# voice_board_kombi.net
KiCad netlist of a schematic drawn in EAGLE
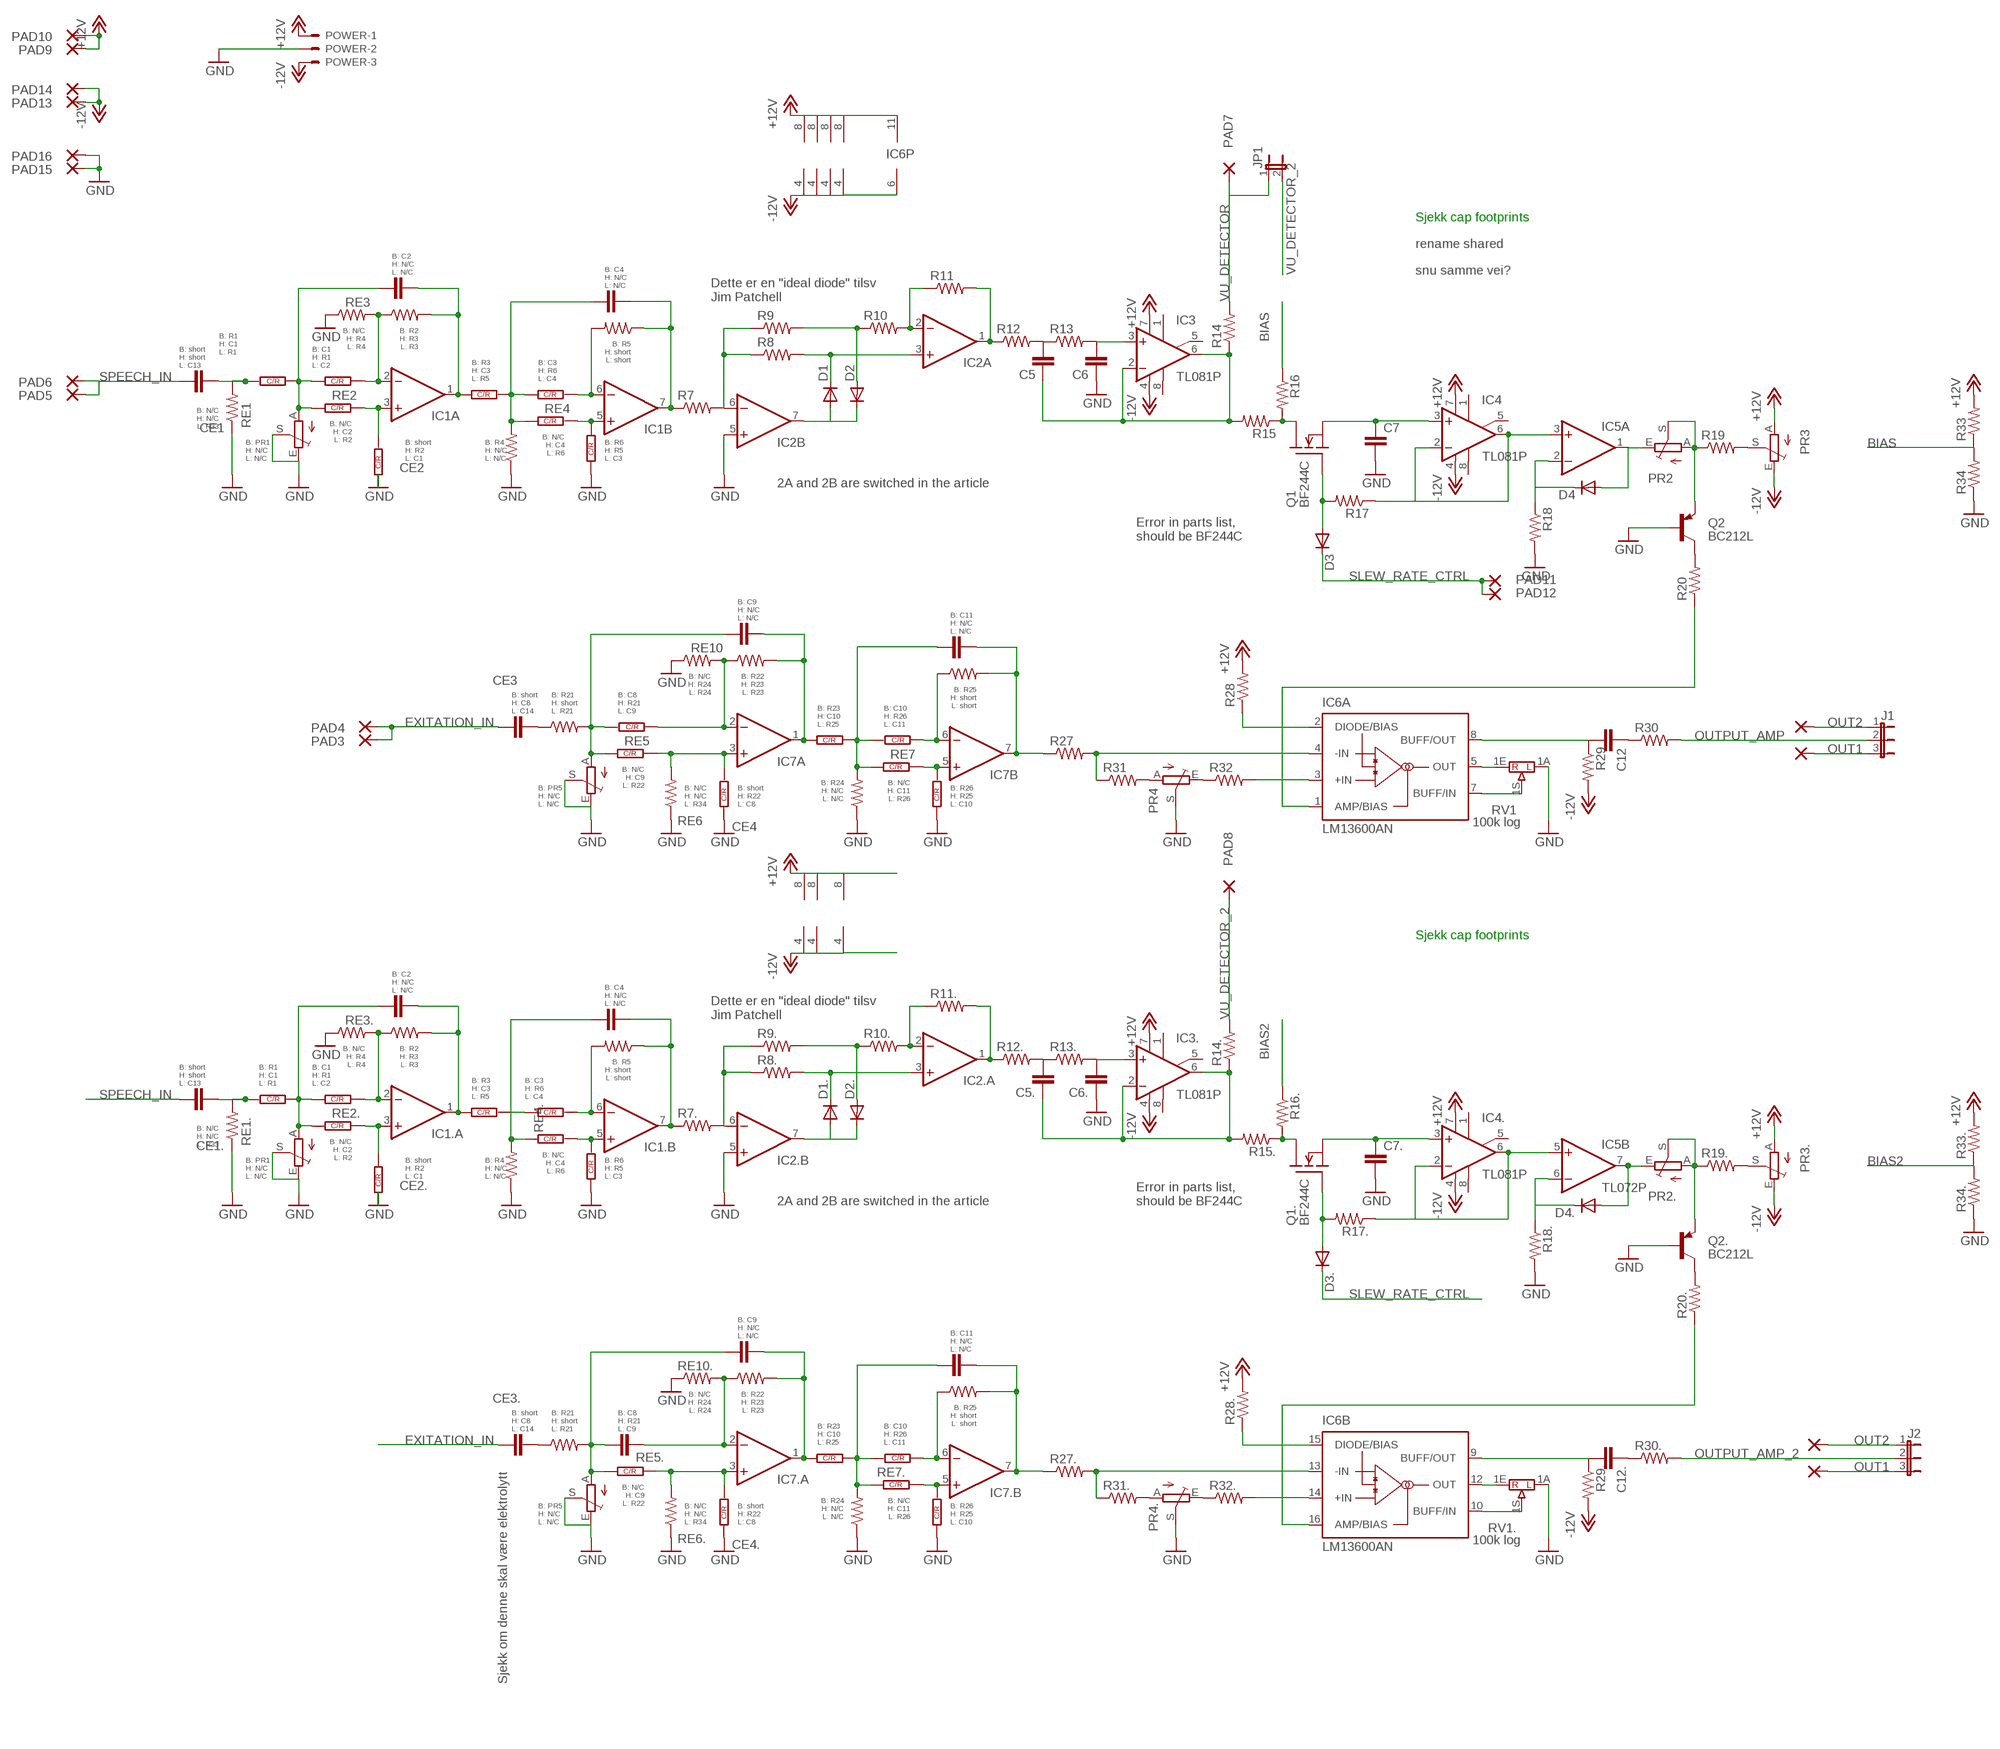
[diagram p0: schematic, sheet 1]

(export (version "E")
  (design (tool "Eeschema 10.0.6"))
  (components
    (comp (ref "C1")
      (value "C-OR-R050_075-025X100")
      (footprint "eagle-import:P050_075-025X100J")
      (libsource (lib "eagle-import") (part "C-OR-R050_075-025X100"))
    )
    (comp (ref "C1.")
      (value "C-OR-R050_075-025X100")
      (footprint "eagle-import:P050_075-025X100J")
      (libsource (lib "eagle-import") (part "C-OR-R050_075-025X100"))
    )
    (comp (ref "C2")
      (value "C-EU050_075-025X100")
      (footprint "eagle-import:C050_075-025X100J")
      (libsource (lib "eagle-import") (part "C-EU050_075-025X100"))
    )
    (comp (ref "C2.")
      (value "C-EU050_075-025X100")
      (footprint "eagle-import:C050_075-025X100J")
      (libsource (lib "eagle-import") (part "C-EU050_075-025X100"))
    )
    (comp (ref "C3")
      (value "C-OR-R050_075-025X100")
      (footprint "eagle-import:P050_075-025X100J")
      (libsource (lib "eagle-import") (part "C-OR-R050_075-025X100"))
    )
    (comp (ref "C3.")
      (value "C-OR-R050_075-025X100")
      (footprint "eagle-import:P050_075-025X100J")
      (libsource (lib "eagle-import") (part "C-OR-R050_075-025X100"))
    )
    (comp (ref "C4")
      (value "C-EU050_075-025X100")
      (footprint "eagle-import:C050_075-025X100J")
      (libsource (lib "eagle-import") (part "C-EU050_075-025X100"))
    )
    (comp (ref "C4.")
      (value "C-EU050_075-025X100")
      (footprint "eagle-import:C050_075-025X100J")
      (libsource (lib "eagle-import") (part "C-EU050_075-025X100"))
    )
    (comp (ref "C5")
      (value "C-EU050_075-025X100")
      (footprint "eagle-import:C050_075-025X100J")
      (libsource (lib "eagle-import") (part "C-EU050_075-025X100"))
    )
    (comp (ref "C5.")
      (value "C-EU050_075-025X100")
      (footprint "eagle-import:C050_075-025X100J")
      (libsource (lib "eagle-import") (part "C-EU050_075-025X100"))
    )
    (comp (ref "C6")
      (value "C-EU050_075-025X100")
      (footprint "eagle-import:C050_075-025X100J")
      (libsource (lib "eagle-import") (part "C-EU050_075-025X100"))
    )
    (comp (ref "C6.")
      (value "C-EU050_075-025X100")
      (footprint "eagle-import:C050_075-025X100J")
      (libsource (lib "eagle-import") (part "C-EU050_075-025X100"))
    )
    (comp (ref "C7")
      (value "C-EU050_075-025X100")
      (footprint "eagle-import:C050_075-025X100J")
      (libsource (lib "eagle-import") (part "C-EU050_075-025X100"))
    )
    (comp (ref "C7.")
      (value "C-EU050_075-025X100")
      (footprint "eagle-import:C050_075-025X100J")
      (libsource (lib "eagle-import") (part "C-EU050_075-025X100"))
    )
    (comp (ref "C8")
      (value "C-OR-R050_075-025X100")
      (footprint "eagle-import:P050_075-025X100J")
      (libsource (lib "eagle-import") (part "C-OR-R050_075-025X100"))
    )
    (comp (ref "C8.")
      (value "C-EU050_075-025X100")
      (footprint "eagle-import:C050_075-025X100J")
      (libsource (lib "eagle-import") (part "C-EU050_075-025X100"))
    )
    (comp (ref "C9")
      (value "C-EU050_075-025X100")
      (footprint "eagle-import:C050_075-025X100J")
      (libsource (lib "eagle-import") (part "C-EU050_075-025X100"))
    )
    (comp (ref "C9.")
      (value "C-EU050_075-025X100")
      (footprint "eagle-import:C050_075-025X100J")
      (libsource (lib "eagle-import") (part "C-EU050_075-025X100"))
    )
    (comp (ref "C10")
      (value "C-OR-R050_075-025X100")
      (footprint "eagle-import:P050_075-025X100J")
      (libsource (lib "eagle-import") (part "C-OR-R050_075-025X100"))
    )
    (comp (ref "C10.")
      (value "C-OR-R050_075-025X100")
      (footprint "eagle-import:P050_075-025X100J")
      (libsource (lib "eagle-import") (part "C-OR-R050_075-025X100"))
    )
    (comp (ref "C11")
      (value "C-EU050_075-025X100")
      (footprint "eagle-import:C050_075-025X100J")
      (libsource (lib "eagle-import") (part "C-EU050_075-025X100"))
    )
    (comp (ref "C11.")
      (value "C-EU050_075-025X100")
      (footprint "eagle-import:C050_075-025X100J")
      (libsource (lib "eagle-import") (part "C-EU050_075-025X100"))
    )
    (comp (ref "C12")
      (value "C-EU050_075-025X100")
      (footprint "eagle-import:C050_075-025X100J")
      (libsource (lib "eagle-import") (part "C-EU050_075-025X100"))
    )
    (comp (ref "C12.")
      (value "C-EU050_075-025X100")
      (footprint "eagle-import:C050_075-025X100J")
      (libsource (lib "eagle-import") (part "C-EU050_075-025X100"))
    )
    (comp (ref "CE1")
      (value "C-EU050_075-025X100")
      (footprint "eagle-import:C050_075-025X100J")
      (libsource (lib "eagle-import") (part "C-EU050_075-025X100"))
    )
    (comp (ref "CE1.")
      (value "C-EU050_075-025X100")
      (footprint "eagle-import:C050_075-025X100J")
      (libsource (lib "eagle-import") (part "C-EU050_075-025X100"))
    )
    (comp (ref "CE2")
      (value "C-OR-R050_075-025X100")
      (footprint "eagle-import:P050_075-025X100J")
      (libsource (lib "eagle-import") (part "C-OR-R050_075-025X100"))
    )
    (comp (ref "CE2.")
      (value "C-OR-R050_075-025X100")
      (footprint "eagle-import:P050_075-025X100J")
      (libsource (lib "eagle-import") (part "C-OR-R050_075-025X100"))
    )
    (comp (ref "CE3")
      (value "C-EU050_075-025X100")
      (footprint "eagle-import:C050_075-025X100J")
      (libsource (lib "eagle-import") (part "C-EU050_075-025X100"))
    )
    (comp (ref "CE3.")
      (value "C-EU050_075-025X100")
      (footprint "eagle-import:C050_075-025X100J")
      (libsource (lib "eagle-import") (part "C-EU050_075-025X100"))
    )
    (comp (ref "CE4")
      (value "C-OR-R050_075-025X100")
      (footprint "eagle-import:P050_075-025X100J")
      (libsource (lib "eagle-import") (part "C-OR-R050_075-025X100"))
    )
    (comp (ref "CE4.")
      (value "C-OR-R050_075-025X100")
      (footprint "eagle-import:P050_075-025X100J")
      (libsource (lib "eagle-import") (part "C-OR-R050_075-025X100"))
    )
    (comp (ref "D1")
      (value "DIODE-D-5")
      (footprint "eagle-import:D-5")
      (libsource (lib "eagle-import") (part "DIODE-D-5"))
    )
    (comp (ref "D1.")
      (value "DIODE-D-5")
      (footprint "eagle-import:D-5")
      (libsource (lib "eagle-import") (part "DIODE-D-5"))
    )
    (comp (ref "D2")
      (value "DIODE-D-5")
      (footprint "eagle-import:D-5")
      (libsource (lib "eagle-import") (part "DIODE-D-5"))
    )
    (comp (ref "D2.")
      (value "DIODE-D-5")
      (footprint "eagle-import:D-5")
      (libsource (lib "eagle-import") (part "DIODE-D-5"))
    )
    (comp (ref "D3")
      (value "DIODE-D-5")
      (footprint "eagle-import:D-5")
      (libsource (lib "eagle-import") (part "DIODE-D-5"))
    )
    (comp (ref "D3.")
      (value "DIODE-D-5")
      (footprint "eagle-import:D-5")
      (libsource (lib "eagle-import") (part "DIODE-D-5"))
    )
    (comp (ref "D4")
      (value "DIODE-D-5")
      (footprint "eagle-import:D-5")
      (libsource (lib "eagle-import") (part "DIODE-D-5"))
    )
    (comp (ref "D4.")
      (value "DIODE-D-5")
      (footprint "eagle-import:D-5")
      (libsource (lib "eagle-import") (part "DIODE-D-5"))
    )
    (comp (ref "IC1")
      (value "TL072P")
      (footprint "eagle-import:DIL08")
      (libsource (lib "eagle-import") (part "TL072P"))
    )
    (comp (ref "IC1.")
      (value "TL072P")
      (footprint "eagle-import:DIL08")
      (libsource (lib "eagle-import") (part "TL072P"))
    )
    (comp (ref "IC2")
      (value "TL072P")
      (footprint "eagle-import:DIL08")
      (libsource (lib "eagle-import") (part "TL072P"))
    )
    (comp (ref "IC2.")
      (value "TL072P")
      (footprint "eagle-import:DIL08")
      (libsource (lib "eagle-import") (part "TL072P"))
    )
    (comp (ref "IC3")
      (value "TL081P")
      (footprint "eagle-import:DIL08")
      (libsource (lib "eagle-import") (part "TL081P"))
    )
    (comp (ref "IC3.")
      (value "TL081P")
      (footprint "eagle-import:DIL08")
      (libsource (lib "eagle-import") (part "TL081P"))
    )
    (comp (ref "IC4")
      (value "TL081P")
      (footprint "eagle-import:DIL08")
      (libsource (lib "eagle-import") (part "TL081P"))
    )
    (comp (ref "IC4.")
      (value "TL081P")
      (footprint "eagle-import:DIL08")
      (libsource (lib "eagle-import") (part "TL081P"))
    )
    (comp (ref "IC5")
      (value "TL072P")
      (footprint "eagle-import:DIL08")
      (libsource (lib "eagle-import") (part "TL072P"))
    )
    (comp (ref "IC6")
      (value "LM13600AN")
      (footprint "eagle-import:DIL16")
      (libsource (lib "eagle-import") (part "LM13600NA"))
    )
    (comp (ref "IC7")
      (value "TL072P")
      (footprint "eagle-import:DIL08")
      (libsource (lib "eagle-import") (part "TL072P"))
    )
    (comp (ref "IC7.")
      (value "TL072P")
      (footprint "eagle-import:DIL08")
      (libsource (lib "eagle-import") (part "TL072P"))
    )
    (comp (ref "J1")
      (value "JP2E")
      (footprint "eagle-import:JP2")
      (libsource (lib "eagle-import") (part "JP2E"))
    )
    (comp (ref "J2")
      (value "JP2E")
      (footprint "eagle-import:JP2")
      (libsource (lib "eagle-import") (part "JP2E"))
    )
    (comp (ref "JP1")
      (value "JP1E")
      (footprint "eagle-import:JP1")
      (libsource (lib "eagle-import") (part "JP1E"))
    )
    (comp (ref "PAD1")
      (value "WIREPAD2,54/1,1")
      (footprint "eagle-import:2,54_1,1")
      (libsource (lib "eagle-import") (part "WIREPAD2,54/1,1"))
    )
    (comp (ref "PAD2")
      (value "WIREPAD2,54/1,1")
      (footprint "eagle-import:2,54_1,1")
      (libsource (lib "eagle-import") (part "WIREPAD2,54/1,1"))
    )
    (comp (ref "PAD3")
      (value "WIREPAD2,54/1,1")
      (footprint "eagle-import:2,54_1,1")
      (libsource (lib "eagle-import") (part "WIREPAD2,54/1,1"))
    )
    (comp (ref "PAD4")
      (value "WIREPAD2,54/1,1")
      (footprint "eagle-import:2,54_1,1")
      (libsource (lib "eagle-import") (part "WIREPAD2,54/1,1"))
    )
    (comp (ref "PAD5")
      (value "WIREPAD2,54/1,1")
      (footprint "eagle-import:2,54_1,1")
      (libsource (lib "eagle-import") (part "WIREPAD2,54/1,1"))
    )
    (comp (ref "PAD6")
      (value "WIREPAD2,54/1,1")
      (footprint "eagle-import:2,54_1,1")
      (libsource (lib "eagle-import") (part "WIREPAD2,54/1,1"))
    )
    (comp (ref "PAD7")
      (value "WIREPAD2,54/1,1")
      (footprint "eagle-import:2,54_1,1")
      (libsource (lib "eagle-import") (part "WIREPAD2,54/1,1"))
    )
    (comp (ref "PAD8")
      (value "WIREPAD2,54/1,1")
      (footprint "eagle-import:2,54_1,1")
      (libsource (lib "eagle-import") (part "WIREPAD2,54/1,1"))
    )
    (comp (ref "PAD9")
      (value "WIREPAD2,54/1,1")
      (footprint "eagle-import:2,54_1,1")
      (libsource (lib "eagle-import") (part "WIREPAD2,54/1,1"))
    )
    (comp (ref "PAD10")
      (value "WIREPAD2,54/1,1")
      (footprint "eagle-import:2,54_1,1")
      (libsource (lib "eagle-import") (part "WIREPAD2,54/1,1"))
    )
    (comp (ref "PAD11")
      (value "WIREPAD2,54/1,1")
      (footprint "eagle-import:2,54_1,1")
      (libsource (lib "eagle-import") (part "WIREPAD2,54/1,1"))
    )
    (comp (ref "PAD12")
      (value "WIREPAD2,54/1,1")
      (footprint "eagle-import:2,54_1,1")
      (libsource (lib "eagle-import") (part "WIREPAD2,54/1,1"))
    )
    (comp (ref "PAD13")
      (value "WIREPAD2,54/1,1")
      (footprint "eagle-import:2,54_1,1")
      (libsource (lib "eagle-import") (part "WIREPAD2,54/1,1"))
    )
    (comp (ref "PAD14")
      (value "WIREPAD2,54/1,1")
      (footprint "eagle-import:2,54_1,1")
      (libsource (lib "eagle-import") (part "WIREPAD2,54/1,1"))
    )
    (comp (ref "PAD15")
      (value "WIREPAD2,54/1,1")
      (footprint "eagle-import:2,54_1,1")
      (libsource (lib "eagle-import") (part "WIREPAD2,54/1,1"))
    )
    (comp (ref "PAD16")
      (value "WIREPAD2,54/1,1")
      (footprint "eagle-import:2,54_1,1")
      (libsource (lib "eagle-import") (part "WIREPAD2,54/1,1"))
    )
    (comp (ref "PAD17")
      (value "WIREPAD2,54/1,1")
      (footprint "eagle-import:2,54_1,1")
      (libsource (lib "eagle-import") (part "WIREPAD2,54/1,1"))
    )
    (comp (ref "PAD18")
      (value "WIREPAD2,54/1,1")
      (footprint "eagle-import:2,54_1,1")
      (libsource (lib "eagle-import") (part "WIREPAD2,54/1,1"))
    )
    (comp (ref "POWER")
      (value "KK-156-3")
      (footprint "eagle-import:KK-156-3")
      (libsource (lib "eagle-import") (part "KK-156-3"))
    )
    (comp (ref "PR1")
      (value "TRIM_EU-CA9V")
      (footprint "eagle-import:CA9V")
      (libsource (lib "eagle-import") (part "TRIM_EU-CA9V"))
    )
    (comp (ref "PR1.")
      (value "TRIM_EU-CA9V")
      (footprint "eagle-import:CA9V")
      (libsource (lib "eagle-import") (part "TRIM_EU-CA9V"))
    )
    (comp (ref "PR2")
      (value "TRIM_EU-CA9V")
      (footprint "eagle-import:CA9V")
      (libsource (lib "eagle-import") (part "TRIM_EU-CA9V"))
    )
    (comp (ref "PR2.")
      (value "TRIM_EU-CA9V")
      (footprint "eagle-import:CA9V")
      (libsource (lib "eagle-import") (part "TRIM_EU-CA9V"))
    )
    (comp (ref "PR3")
      (value "TRIM_EU-CA9V")
      (footprint "eagle-import:CA9V")
      (libsource (lib "eagle-import") (part "TRIM_EU-CA9V"))
    )
    (comp (ref "PR3.")
      (value "TRIM_EU-CA9V")
      (footprint "eagle-import:CA9V")
      (libsource (lib "eagle-import") (part "TRIM_EU-CA9V"))
    )
    (comp (ref "PR4")
      (value "TRIM_EU-CA9V")
      (footprint "eagle-import:CA9V")
      (libsource (lib "eagle-import") (part "TRIM_EU-CA9V"))
    )
    (comp (ref "PR4.")
      (value "TRIM_EU-CA9V")
      (footprint "eagle-import:CA9V")
      (libsource (lib "eagle-import") (part "TRIM_EU-CA9V"))
    )
    (comp (ref "PR5")
      (value "TRIM_EU-CA9V")
      (footprint "eagle-import:CA9V")
      (libsource (lib "eagle-import") (part "TRIM_EU-CA9V"))
    )
    (comp (ref "PR5.")
      (value "TRIM_EU-CA9V")
      (footprint "eagle-import:CA9V")
      (libsource (lib "eagle-import") (part "TRIM_EU-CA9V"))
    )
    (comp (ref "Q1")
      (value "BF244C")
      (footprint "eagle-import:TO-92")
      (libsource (lib "eagle-import") (part "TN0602N3"))
    )
    (comp (ref "Q1.")
      (value "BF244C")
      (footprint "eagle-import:TO-92")
      (libsource (lib "eagle-import") (part "TN0602N3"))
    )
    (comp (ref "Q2")
      (value "BC212L")
      (footprint "eagle-import:TO92-ECB")
      (libsource (lib "eagle-import") (part "-PNP-TO92-ECB"))
    )
    (comp (ref "Q2.")
      (value "BC212L")
      (footprint "eagle-import:TO92-ECB")
      (libsource (lib "eagle-import") (part "-PNP-TO92-ECB"))
    )
    (comp (ref "R1")
      (value "C-OR-R050_075-025X100")
      (footprint "eagle-import:P050_075-025X100J")
      (libsource (lib "eagle-import") (part "C-OR-R050_075-025X100"))
    )
    (comp (ref "R1.")
      (value "C-OR-R050_075-025X100")
      (footprint "eagle-import:P050_075-025X100J")
      (libsource (lib "eagle-import") (part "C-OR-R050_075-025X100"))
    )
    (comp (ref "R2")
      (value "R-US_0207/7")
      (footprint "eagle-import:0207_7")
      (libsource (lib "eagle-import") (part "R-US_0207/7"))
    )
    (comp (ref "R2.")
      (value "R-US_0207/7")
      (footprint "eagle-import:0207_7")
      (libsource (lib "eagle-import") (part "R-US_0207/7"))
    )
    (comp (ref "R3")
      (value "C-OR-R050_075-025X100")
      (footprint "eagle-import:P050_075-025X100J")
      (libsource (lib "eagle-import") (part "C-OR-R050_075-025X100"))
    )
    (comp (ref "R3.")
      (value "C-OR-R050_075-025X100")
      (footprint "eagle-import:P050_075-025X100J")
      (libsource (lib "eagle-import") (part "C-OR-R050_075-025X100"))
    )
    (comp (ref "R4")
      (value "R-US_0207/7")
      (footprint "eagle-import:0207_7")
      (libsource (lib "eagle-import") (part "R-US_0207/7"))
    )
    (comp (ref "R4.")
      (value "R-US_0207/7")
      (footprint "eagle-import:0207_7")
      (libsource (lib "eagle-import") (part "R-US_0207/7"))
    )
    (comp (ref "R5")
      (value "R-US_0207/7")
      (footprint "eagle-import:0207_7")
      (libsource (lib "eagle-import") (part "R-US_0207/7"))
    )
    (comp (ref "R5.")
      (value "R-US_0207/7")
      (footprint "eagle-import:0207_7")
      (libsource (lib "eagle-import") (part "R-US_0207/7"))
    )
    (comp (ref "R6")
      (value "C-OR-R050_075-025X100")
      (footprint "eagle-import:P050_075-025X100J")
      (libsource (lib "eagle-import") (part "C-OR-R050_075-025X100"))
    )
    (comp (ref "R6.")
      (value "C-OR-R050_075-025X100")
      (footprint "eagle-import:P050_075-025X100J")
      (libsource (lib "eagle-import") (part "C-OR-R050_075-025X100"))
    )
    (comp (ref "R7")
      (value "R-US_0207/7")
      (footprint "eagle-import:0207_7")
      (libsource (lib "eagle-import") (part "R-US_0207/7"))
    )
    (comp (ref "R7.")
      (value "R-US_0207/7")
      (footprint "eagle-import:0207_7")
      (libsource (lib "eagle-import") (part "R-US_0207/7"))
    )
    (comp (ref "R8")
      (value "R-US_0207/7")
      (footprint "eagle-import:0207_7")
      (libsource (lib "eagle-import") (part "R-US_0207/7"))
    )
    (comp (ref "R8.")
      (value "R-US_0207/7")
      (footprint "eagle-import:0207_7")
      (libsource (lib "eagle-import") (part "R-US_0207/7"))
    )
    (comp (ref "R9")
      (value "R-US_0207/7")
      (footprint "eagle-import:0207_7")
      (libsource (lib "eagle-import") (part "R-US_0207/7"))
    )
    (comp (ref "R9.")
      (value "R-US_0207/7")
      (footprint "eagle-import:0207_7")
      (libsource (lib "eagle-import") (part "R-US_0207/7"))
    )
    (comp (ref "R10")
      (value "R-US_0207/7")
      (footprint "eagle-import:0207_7")
      (libsource (lib "eagle-import") (part "R-US_0207/7"))
    )
    (comp (ref "R10.")
      (value "R-US_0207/7")
      (footprint "eagle-import:0207_7")
      (libsource (lib "eagle-import") (part "R-US_0207/7"))
    )
    (comp (ref "R11")
      (value "R-US_0207/7")
      (footprint "eagle-import:0207_7")
      (libsource (lib "eagle-import") (part "R-US_0207/7"))
    )
    (comp (ref "R11.")
      (value "R-US_0207/7")
      (footprint "eagle-import:0207_7")
      (libsource (lib "eagle-import") (part "R-US_0207/7"))
    )
    (comp (ref "R12")
      (value "R-US_0207/7")
      (footprint "eagle-import:0207_7")
      (libsource (lib "eagle-import") (part "R-US_0207/7"))
    )
    (comp (ref "R12.")
      (value "R-US_0207/7")
      (footprint "eagle-import:0207_7")
      (libsource (lib "eagle-import") (part "R-US_0207/7"))
    )
    (comp (ref "R13")
      (value "R-US_0207/7")
      (footprint "eagle-import:0207_7")
      (libsource (lib "eagle-import") (part "R-US_0207/7"))
    )
    (comp (ref "R13.")
      (value "R-US_0207/7")
      (footprint "eagle-import:0207_7")
      (libsource (lib "eagle-import") (part "R-US_0207/7"))
    )
    (comp (ref "R14")
      (value "R-US_0207/7")
      (footprint "eagle-import:0207_7")
      (libsource (lib "eagle-import") (part "R-US_0207/7"))
    )
    (comp (ref "R14.")
      (value "R-US_0207/7")
      (footprint "eagle-import:0207_7")
      (libsource (lib "eagle-import") (part "R-US_0207/7"))
    )
    (comp (ref "R15")
      (value "R-US_0207/7")
      (footprint "eagle-import:0207_7")
      (libsource (lib "eagle-import") (part "R-US_0207/7"))
    )
    (comp (ref "R15.")
      (value "R-US_0207/7")
      (footprint "eagle-import:0207_7")
      (libsource (lib "eagle-import") (part "R-US_0207/7"))
    )
    (comp (ref "R16")
      (value "R-US_0207/7")
      (footprint "eagle-import:0207_7")
      (libsource (lib "eagle-import") (part "R-US_0207/7"))
    )
    (comp (ref "R16.")
      (value "R-US_0207/7")
      (footprint "eagle-import:0207_7")
      (libsource (lib "eagle-import") (part "R-US_0207/7"))
    )
    (comp (ref "R17")
      (value "R-US_0207/7")
      (footprint "eagle-import:0207_7")
      (libsource (lib "eagle-import") (part "R-US_0207/7"))
    )
    (comp (ref "R17.")
      (value "R-US_0207/7")
      (footprint "eagle-import:0207_7")
      (libsource (lib "eagle-import") (part "R-US_0207/7"))
    )
    (comp (ref "R18")
      (value "R-US_0207/7")
      (footprint "eagle-import:0207_7")
      (libsource (lib "eagle-import") (part "R-US_0207/7"))
    )
    (comp (ref "R18.")
      (value "R-US_0207/7")
      (footprint "eagle-import:0207_7")
      (libsource (lib "eagle-import") (part "R-US_0207/7"))
    )
    (comp (ref "R19")
      (value "R-US_0207/7")
      (footprint "eagle-import:0207_7")
      (libsource (lib "eagle-import") (part "R-US_0207/7"))
    )
    (comp (ref "R19.")
      (value "R-US_0207/7")
      (footprint "eagle-import:0207_7")
      (libsource (lib "eagle-import") (part "R-US_0207/7"))
    )
    (comp (ref "R20")
      (value "R-US_0207/7")
      (footprint "eagle-import:0207_7")
      (libsource (lib "eagle-import") (part "R-US_0207/7"))
    )
    (comp (ref "R20.")
      (value "R-US_0207/7")
      (footprint "eagle-import:0207_7")
      (libsource (lib "eagle-import") (part "R-US_0207/7"))
    )
    (comp (ref "R21")
      (value "R-US_0207/7")
      (footprint "eagle-import:0207_7")
      (libsource (lib "eagle-import") (part "R-US_0207/7"))
    )
    (comp (ref "R21.")
      (value "R-US_0207/7")
      (footprint "eagle-import:0207_7")
      (libsource (lib "eagle-import") (part "R-US_0207/7"))
    )
    (comp (ref "R22")
      (value "R-US_0207/7")
      (footprint "eagle-import:0207_7")
      (libsource (lib "eagle-import") (part "R-US_0207/7"))
    )
    (comp (ref "R22.")
      (value "R-US_0207/7")
      (footprint "eagle-import:0207_7")
      (libsource (lib "eagle-import") (part "R-US_0207/7"))
    )
    (comp (ref "R23")
      (value "C-OR-R050_075-025X100")
      (footprint "eagle-import:P050_075-025X100J")
      (libsource (lib "eagle-import") (part "C-OR-R050_075-025X100"))
    )
    (comp (ref "R23.")
      (value "C-OR-R050_075-025X100")
      (footprint "eagle-import:P050_075-025X100J")
      (libsource (lib "eagle-import") (part "C-OR-R050_075-025X100"))
    )
    (comp (ref "R24")
      (value "R-US_0207/7")
      (footprint "eagle-import:0207_7")
      (libsource (lib "eagle-import") (part "R-US_0207/7"))
    )
    (comp (ref "R24.")
      (value "R-US_0207/7")
      (footprint "eagle-import:0207_7")
      (libsource (lib "eagle-import") (part "R-US_0207/7"))
    )
    (comp (ref "R25")
      (value "R-US_0207/7")
      (footprint "eagle-import:0207_7")
      (libsource (lib "eagle-import") (part "R-US_0207/7"))
    )
    (comp (ref "R25.")
      (value "R-US_0207/7")
      (footprint "eagle-import:0207_7")
      (libsource (lib "eagle-import") (part "R-US_0207/7"))
    )
    (comp (ref "R26")
      (value "C-OR-R050_075-025X100")
      (footprint "eagle-import:P050_075-025X100J")
      (libsource (lib "eagle-import") (part "C-OR-R050_075-025X100"))
    )
    (comp (ref "R26.")
      (value "C-OR-R050_075-025X100")
      (footprint "eagle-import:P050_075-025X100J")
      (libsource (lib "eagle-import") (part "C-OR-R050_075-025X100"))
    )
    (comp (ref "R27")
      (value "R-US_0207/7")
      (footprint "eagle-import:0207_7")
      (libsource (lib "eagle-import") (part "R-US_0207/7"))
    )
    (comp (ref "R27.")
      (value "R-US_0207/7")
      (footprint "eagle-import:0207_7")
      (libsource (lib "eagle-import") (part "R-US_0207/7"))
    )
    (comp (ref "R28")
      (value "R-US_0207/7")
      (footprint "eagle-import:0207_7")
      (libsource (lib "eagle-import") (part "R-US_0207/7"))
    )
    (comp (ref "R28.")
      (value "R-US_0207/7")
      (footprint "eagle-import:0207_7")
      (libsource (lib "eagle-import") (part "R-US_0207/7"))
    )
    (comp (ref "R29")
      (value "R-US_0207/7")
      (footprint "eagle-import:0207_7")
      (libsource (lib "eagle-import") (part "R-US_0207/7"))
    )
    (comp (ref "R29.")
      (value "R-US_0207/7")
      (footprint "eagle-import:0207_7")
      (libsource (lib "eagle-import") (part "R-US_0207/7"))
    )
    (comp (ref "R30")
      (value "R-US_0207/7")
      (footprint "eagle-import:0207_7")
      (libsource (lib "eagle-import") (part "R-US_0207/7"))
    )
    (comp (ref "R30.")
      (value "R-US_0207/7")
      (footprint "eagle-import:0207_7")
      (libsource (lib "eagle-import") (part "R-US_0207/7"))
    )
    (comp (ref "R31")
      (value "R-US_0207/7")
      (footprint "eagle-import:0207_7")
      (libsource (lib "eagle-import") (part "R-US_0207/7"))
    )
    (comp (ref "R31.")
      (value "R-US_0207/7")
      (footprint "eagle-import:0207_7")
      (libsource (lib "eagle-import") (part "R-US_0207/7"))
    )
    (comp (ref "R32")
      (value "R-US_0207/7")
      (footprint "eagle-import:0207_7")
      (libsource (lib "eagle-import") (part "R-US_0207/7"))
    )
    (comp (ref "R32.")
      (value "R-US_0207/7")
      (footprint "eagle-import:0207_7")
      (libsource (lib "eagle-import") (part "R-US_0207/7"))
    )
    (comp (ref "R33")
      (value "R-US_0207/7")
      (footprint "eagle-import:0207_7")
      (libsource (lib "eagle-import") (part "R-US_0207/7"))
    )
    (comp (ref "R33.")
      (value "R-US_0207/7")
      (footprint "eagle-import:0207_7")
      (libsource (lib "eagle-import") (part "R-US_0207/7"))
    )
    (comp (ref "R34")
      (value "R-US_0207/7")
      (footprint "eagle-import:0207_7")
      (libsource (lib "eagle-import") (part "R-US_0207/7"))
    )
    (comp (ref "R34.")
      (value "R-US_0207/7")
      (footprint "eagle-import:0207_7")
      (libsource (lib "eagle-import") (part "R-US_0207/7"))
    )
    (comp (ref "RE1")
      (value "R-US_0207/7")
      (footprint "eagle-import:0207_7")
      (libsource (lib "eagle-import") (part "R-US_0207/7"))
    )
    (comp (ref "RE1.")
      (value "R-US_0207/7")
      (footprint "eagle-import:0207_7")
      (libsource (lib "eagle-import") (part "R-US_0207/7"))
    )
    (comp (ref "RE2")
      (value "C-OR-R050_075-025X100")
      (footprint "eagle-import:P050_075-025X100J")
      (libsource (lib "eagle-import") (part "C-OR-R050_075-025X100"))
    )
    (comp (ref "RE2.")
      (value "C-OR-R050_075-025X100")
      (footprint "eagle-import:P050_075-025X100J")
      (libsource (lib "eagle-import") (part "C-OR-R050_075-025X100"))
    )
    (comp (ref "RE3")
      (value "R-US_0207/7")
      (footprint "eagle-import:0207_7")
      (libsource (lib "eagle-import") (part "R-US_0207/7"))
    )
    (comp (ref "RE3.")
      (value "R-US_0207/7")
      (footprint "eagle-import:0207_7")
      (libsource (lib "eagle-import") (part "R-US_0207/7"))
    )
    (comp (ref "RE4")
      (value "C-OR-R050_075-025X100")
      (footprint "eagle-import:P050_075-025X100J")
      (libsource (lib "eagle-import") (part "C-OR-R050_075-025X100"))
    )
    (comp (ref "RE4.")
      (value "C-OR-R050_075-025X100")
      (footprint "eagle-import:P050_075-025X100J")
      (libsource (lib "eagle-import") (part "C-OR-R050_075-025X100"))
    )
    (comp (ref "RE5")
      (value "C-OR-R050_075-025X100")
      (footprint "eagle-import:P050_075-025X100J")
      (libsource (lib "eagle-import") (part "C-OR-R050_075-025X100"))
    )
    (comp (ref "RE5.")
      (value "C-OR-R050_075-025X100")
      (footprint "eagle-import:P050_075-025X100J")
      (libsource (lib "eagle-import") (part "C-OR-R050_075-025X100"))
    )
    (comp (ref "RE6")
      (value "R-US_0207/7")
      (footprint "eagle-import:0207_7")
      (libsource (lib "eagle-import") (part "R-US_0207/7"))
    )
    (comp (ref "RE6.")
      (value "R-US_0207/7")
      (footprint "eagle-import:0207_7")
      (libsource (lib "eagle-import") (part "R-US_0207/7"))
    )
    (comp (ref "RE7")
      (value "C-OR-R050_075-025X100")
      (footprint "eagle-import:P050_075-025X100J")
      (libsource (lib "eagle-import") (part "C-OR-R050_075-025X100"))
    )
    (comp (ref "RE7.")
      (value "C-OR-R050_075-025X100")
      (footprint "eagle-import:P050_075-025X100J")
      (libsource (lib "eagle-import") (part "C-OR-R050_075-025X100"))
    )
    (comp (ref "RE10")
      (value "R-US_0207/7")
      (footprint "eagle-import:0207_7")
      (libsource (lib "eagle-import") (part "R-US_0207/7"))
    )
    (comp (ref "RE10.")
      (value "R-US_0207/7")
      (footprint "eagle-import:0207_7")
      (libsource (lib "eagle-import") (part "R-US_0207/7"))
    )
    (comp (ref "RV1")
      (value "100k log")
      (footprint "eagle-import:POT16_W_BRACKET")
      (libsource (lib "eagle-import") (part "POT16_W_BRACKET{dblquote}{dblquote}"))
    )
    (comp (ref "RV1.")
      (value "100k log")
      (footprint "eagle-import:POT16_W_BRACKET")
      (libsource (lib "eagle-import") (part "POT16_W_BRACKET{dblquote}{dblquote}"))
    )
  )
  (nets
    (net (code "1") (name "+12V") (class "Default")
      (node (ref "IC1") (pin "8") (pinfunction "V+_8") (pintype "power_in"))
      (node (ref "IC1.") (pin "8") (pinfunction "V+_8") (pintype "power_in"))
      (node (ref "IC2") (pin "8") (pinfunction "V+_8") (pintype "power_in"))
      (node (ref "IC2.") (pin "8") (pinfunction "V+_8") (pintype "power_in"))
      (node (ref "IC3") (pin "7") (pinfunction "V+_7") (pintype "power_in"))
      (node (ref "IC3.") (pin "7") (pinfunction "V+_7") (pintype "power_in"))
      (node (ref "IC4") (pin "7") (pinfunction "V+_7") (pintype "power_in"))
      (node (ref "IC4.") (pin "7") (pinfunction "V+_7") (pintype "power_in"))
      (node (ref "IC5") (pin "8") (pinfunction "V+_8") (pintype "power_in"))
      (node (ref "IC6") (pin "11") (pinfunction "V+_11") (pintype "power_in"))
      (node (ref "IC7") (pin "8") (pinfunction "V+_8") (pintype "power_in"))
      (node (ref "IC7.") (pin "8") (pinfunction "V+_8") (pintype "power_in"))
      (node (ref "PAD10") (pin "1") (pinfunction "P_1") (pintype "passive"))
      (node (ref "PAD9") (pin "1") (pinfunction "P_1") (pintype "passive"))
      (node (ref "POWER") (pin "1") (pinfunction "S_1") (pintype "passive"))
      (node (ref "PR3") (pin "A") (pinfunction "A_A") (pintype "passive"))
      (node (ref "PR3.") (pin "A") (pinfunction "A_A") (pintype "passive"))
      (node (ref "R28") (pin "2") (pinfunction "2_2") (pintype "passive"))
      (node (ref "R28.") (pin "2") (pinfunction "2_2") (pintype "passive"))
      (node (ref "R33") (pin "2") (pinfunction "2_2") (pintype "passive"))
      (node (ref "R33.") (pin "2") (pinfunction "2_2") (pintype "passive"))
    )
    (net (code "2") (name "-12V") (class "Default")
      (node (ref "IC1") (pin "4") (pinfunction "V-_4") (pintype "power_in"))
      (node (ref "IC1.") (pin "4") (pinfunction "V-_4") (pintype "power_in"))
      (node (ref "IC2") (pin "4") (pinfunction "V-_4") (pintype "power_in"))
      (node (ref "IC2.") (pin "4") (pinfunction "V-_4") (pintype "power_in"))
      (node (ref "IC3") (pin "4") (pinfunction "V-_4") (pintype "power_in"))
      (node (ref "IC3.") (pin "4") (pinfunction "V-_4") (pintype "power_in"))
      (node (ref "IC4") (pin "4") (pinfunction "V-_4") (pintype "power_in"))
      (node (ref "IC4.") (pin "4") (pinfunction "V-_4") (pintype "power_in"))
      (node (ref "IC5") (pin "4") (pinfunction "V-_4") (pintype "power_in"))
      (node (ref "IC6") (pin "6") (pinfunction "V-_6") (pintype "power_in"))
      (node (ref "IC7") (pin "4") (pinfunction "V-_4") (pintype "power_in"))
      (node (ref "IC7.") (pin "4") (pinfunction "V-_4") (pintype "power_in"))
      (node (ref "PAD13") (pin "1") (pinfunction "P_1") (pintype "passive"))
      (node (ref "PAD14") (pin "1") (pinfunction "P_1") (pintype "passive"))
      (node (ref "POWER") (pin "3") (pinfunction "S_3") (pintype "passive"))
      (node (ref "PR3") (pin "E") (pinfunction "E_E") (pintype "passive"))
      (node (ref "PR3.") (pin "E") (pinfunction "E_E") (pintype "passive"))
      (node (ref "R29") (pin "2") (pinfunction "2_2") (pintype "passive"))
      (node (ref "R29.") (pin "2") (pinfunction "2_2") (pintype "passive"))
    )
    (net (code "3") (name "/BIAS") (class "Default")
      (node (ref "R16") (pin "1") (pinfunction "1_1") (pintype "passive"))
      (node (ref "R33") (pin "1") (pinfunction "1_1") (pintype "passive"))
      (node (ref "R34") (pin "2") (pinfunction "2_2") (pintype "passive"))
    )
    (net (code "4") (name "/BIAS2") (class "Default")
      (node (ref "R16.") (pin "1") (pinfunction "1_1") (pintype "passive"))
      (node (ref "R33.") (pin "1") (pinfunction "1_1") (pintype "passive"))
      (node (ref "R34.") (pin "2") (pinfunction "2_2") (pintype "passive"))
    )
    (net (code "5") (name "/EXITATION_IN") (class "Default")
      (node (ref "CE3") (pin "1") (pinfunction "1_1") (pintype "passive"))
      (node (ref "CE3.") (pin "1") (pinfunction "1_1") (pintype "passive"))
      (node (ref "PAD3") (pin "1") (pinfunction "P_1") (pintype "passive"))
      (node (ref "PAD4") (pin "1") (pinfunction "P_1") (pintype "passive"))
    )
    (net (code "6") (name "/OUT1") (class "Default")
      (node (ref "J1") (pin "3") (pinfunction "3_3") (pintype "passive"))
      (node (ref "J2") (pin "3") (pinfunction "3_3") (pintype "passive"))
      (node (ref "PAD1") (pin "1") (pinfunction "P_1") (pintype "passive"))
      (node (ref "PAD2") (pin "1") (pinfunction "P_1") (pintype "passive"))
    )
    (net (code "7") (name "/OUT2") (class "Default")
      (node (ref "J1") (pin "1") (pinfunction "1_1") (pintype "passive"))
      (node (ref "J2") (pin "1") (pinfunction "1_1") (pintype "passive"))
      (node (ref "PAD17") (pin "1") (pinfunction "P_1") (pintype "passive"))
      (node (ref "PAD18") (pin "1") (pinfunction "P_1") (pintype "passive"))
    )
    (net (code "8") (name "/OUTPUT_AMP") (class "Default")
      (node (ref "J1") (pin "2") (pinfunction "2_2") (pintype "passive"))
      (node (ref "R30") (pin "2") (pinfunction "2_2") (pintype "passive"))
    )
    (net (code "9") (name "/OUTPUT_AMP_2") (class "Default")
      (node (ref "J2") (pin "2") (pinfunction "2_2") (pintype "passive"))
      (node (ref "R30.") (pin "2") (pinfunction "2_2") (pintype "passive"))
    )
    (net (code "10") (name "/SLEW_RATE_CTRL") (class "Default")
      (node (ref "D3") (pin "C") (pinfunction "C_C") (pintype "passive"))
      (node (ref "D3.") (pin "C") (pinfunction "C_C") (pintype "passive"))
      (node (ref "PAD11") (pin "1") (pinfunction "P_1") (pintype "passive"))
      (node (ref "PAD12") (pin "1") (pinfunction "P_1") (pintype "passive"))
    )
    (net (code "11") (name "/SPEECH_IN") (class "Default")
      (node (ref "CE1") (pin "2") (pinfunction "2_2") (pintype "passive"))
      (node (ref "CE1") (pin "3") (pinfunction "2_3") (pintype "passive"))
      (node (ref "CE1.") (pin "2") (pinfunction "2_2") (pintype "passive"))
      (node (ref "CE1.") (pin "3") (pinfunction "2_3") (pintype "passive"))
      (node (ref "PAD5") (pin "1") (pinfunction "P_1") (pintype "passive"))
      (node (ref "PAD6") (pin "1") (pinfunction "P_1") (pintype "passive"))
    )
    (net (code "12") (name "/VU_DETECTOR") (class "Default")
      (node (ref "JP1") (pin "1") (pinfunction "1_1") (pintype "passive"))
      (node (ref "PAD7") (pin "1") (pinfunction "P_1") (pintype "passive"))
      (node (ref "R14") (pin "2") (pinfunction "2_2") (pintype "passive"))
    )
    (net (code "13") (name "/VU_DETECTOR_2") (class "Default")
      (node (ref "JP1") (pin "2") (pinfunction "2_2") (pintype "passive"))
      (node (ref "PAD8") (pin "1") (pinfunction "P_1") (pintype "passive"))
      (node (ref "R14.") (pin "2") (pinfunction "2_2") (pintype "passive"))
    )
    (net (code "14") (name "GND") (class "Default")
      (node (ref "C6") (pin "1") (pinfunction "1_1") (pintype "passive"))
      (node (ref "C6.") (pin "1") (pinfunction "1_1") (pintype "passive"))
      (node (ref "C7") (pin "2") (pinfunction "2_2") (pintype "passive"))
      (node (ref "C7") (pin "3") (pinfunction "2_3") (pintype "passive"))
      (node (ref "C7.") (pin "2") (pinfunction "2_2") (pintype "passive"))
      (node (ref "C7.") (pin "3") (pinfunction "2_3") (pintype "passive"))
      (node (ref "CE2") (pin "1") (pinfunction "1_1") (pintype "passive"))
      (node (ref "CE2.") (pin "1") (pinfunction "1_1") (pintype "passive"))
      (node (ref "CE4") (pin "1") (pinfunction "1_1") (pintype "passive"))
      (node (ref "CE4.") (pin "1") (pinfunction "1_1") (pintype "passive"))
      (node (ref "IC2") (pin "5") (pinfunction "+IN_5") (pintype "input"))
      (node (ref "IC2.") (pin "5") (pinfunction "+IN_5") (pintype "input"))
      (node (ref "PAD15") (pin "1") (pinfunction "P_1") (pintype "passive"))
      (node (ref "PAD16") (pin "1") (pinfunction "P_1") (pintype "passive"))
      (node (ref "POWER") (pin "2") (pinfunction "S_2") (pintype "passive"))
      (node (ref "PR1") (pin "E") (pinfunction "E_E") (pintype "passive"))
      (node (ref "PR1") (pin "S") (pinfunction "S_S") (pintype "passive"))
      (node (ref "PR1.") (pin "E") (pinfunction "E_E") (pintype "passive"))
      (node (ref "PR1.") (pin "S") (pinfunction "S_S") (pintype "passive"))
      (node (ref "PR4") (pin "S") (pinfunction "S_S") (pintype "passive"))
      (node (ref "PR4.") (pin "S") (pinfunction "S_S") (pintype "passive"))
      (node (ref "PR5") (pin "E") (pinfunction "E_E") (pintype "passive"))
      (node (ref "PR5") (pin "S") (pinfunction "S_S") (pintype "passive"))
      (node (ref "PR5.") (pin "E") (pinfunction "E_E") (pintype "passive"))
      (node (ref "PR5.") (pin "S") (pinfunction "S_S") (pintype "passive"))
      (node (ref "Q2") (pin "B") (pinfunction "B_B") (pintype "passive"))
      (node (ref "Q2.") (pin "B") (pinfunction "B_B") (pintype "passive"))
      (node (ref "R18") (pin "2") (pinfunction "2_2") (pintype "passive"))
      (node (ref "R18.") (pin "2") (pinfunction "2_2") (pintype "passive"))
      (node (ref "R24") (pin "1") (pinfunction "1_1") (pintype "passive"))
      (node (ref "R24.") (pin "1") (pinfunction "1_1") (pintype "passive"))
      (node (ref "R26") (pin "1") (pinfunction "1_1") (pintype "passive"))
      (node (ref "R26.") (pin "1") (pinfunction "1_1") (pintype "passive"))
      (node (ref "R34") (pin "1") (pinfunction "1_1") (pintype "passive"))
      (node (ref "R34.") (pin "1") (pinfunction "1_1") (pintype "passive"))
      (node (ref "R4") (pin "1") (pinfunction "1_1") (pintype "passive"))
      (node (ref "R4.") (pin "1") (pinfunction "1_1") (pintype "passive"))
      (node (ref "R6") (pin "1") (pinfunction "1_1") (pintype "passive"))
      (node (ref "R6.") (pin "1") (pinfunction "1_1") (pintype "passive"))
      (node (ref "RE1") (pin "1") (pinfunction "1_1") (pintype "passive"))
      (node (ref "RE1.") (pin "1") (pinfunction "1_1") (pintype "passive"))
      (node (ref "RE10") (pin "1") (pinfunction "1_1") (pintype "passive"))
      (node (ref "RE10.") (pin "1") (pinfunction "1_1") (pintype "passive"))
      (node (ref "RE3") (pin "1") (pinfunction "1_1") (pintype "passive"))
      (node (ref "RE3.") (pin "1") (pinfunction "1_1") (pintype "passive"))
      (node (ref "RE6") (pin "1") (pinfunction "1_1") (pintype "passive"))
      (node (ref "RE6.") (pin "1") (pinfunction "1_1") (pintype "passive"))
      (node (ref "RV1") (pin "1A") (pinfunction "1A_1A") (pintype "passive"))
      (node (ref "RV1.") (pin "1A") (pinfunction "1A_1A") (pintype "passive"))
    )
    (net (code "15") (name "Net-(C1-Pad1)") (class "Default")
      (node (ref "C1") (pin "1") (pinfunction "1_1") (pintype "passive"))
      (node (ref "C2") (pin "1") (pinfunction "1_1") (pintype "passive"))
      (node (ref "PR1") (pin "A") (pinfunction "A_A") (pintype "passive"))
      (node (ref "R1") (pin "1") (pinfunction "1_1") (pintype "passive"))
      (node (ref "RE2") (pin "1") (pinfunction "1_1") (pintype "passive"))
    )
    (net (code "16") (name "Net-(C1.-Pad1)") (class "Default")
      (node (ref "C1.") (pin "1") (pinfunction "1_1") (pintype "passive"))
      (node (ref "C2.") (pin "1") (pinfunction "1_1") (pintype "passive"))
      (node (ref "PR1.") (pin "A") (pinfunction "A_A") (pintype "passive"))
      (node (ref "R1.") (pin "1") (pinfunction "1_1") (pintype "passive"))
      (node (ref "RE2.") (pin "1") (pinfunction "1_1") (pintype "passive"))
    )
    (net (code "17") (name "Net-(C3-Pad1)") (class "Default")
      (node (ref "C3") (pin "1") (pinfunction "1_1") (pintype "passive"))
      (node (ref "C4") (pin "1") (pinfunction "1_1") (pintype "passive"))
      (node (ref "R3") (pin "2") (pinfunction "2_2") (pintype "passive"))
      (node (ref "R3") (pin "3") (pinfunction "2_3") (pintype "passive"))
      (node (ref "R4") (pin "2") (pinfunction "2_2") (pintype "passive"))
      (node (ref "RE4") (pin "1") (pinfunction "1_1") (pintype "passive"))
    )
    (net (code "18") (name "Net-(C3.-Pad1)") (class "Default")
      (node (ref "C3.") (pin "1") (pinfunction "1_1") (pintype "passive"))
      (node (ref "C4.") (pin "1") (pinfunction "1_1") (pintype "passive"))
      (node (ref "R3.") (pin "2") (pinfunction "2_2") (pintype "passive"))
      (node (ref "R3.") (pin "3") (pinfunction "2_3") (pintype "passive"))
      (node (ref "R4.") (pin "2") (pinfunction "2_2") (pintype "passive"))
      (node (ref "RE4.") (pin "1") (pinfunction "1_1") (pintype "passive"))
    )
    (net (code "19") (name "Net-(C5-2-Pad3)") (class "Default")
      (node (ref "C5") (pin "2") (pinfunction "2_2") (pintype "passive"))
      (node (ref "C5") (pin "3") (pinfunction "2_3") (pintype "passive"))
      (node (ref "R12") (pin "2") (pinfunction "2_2") (pintype "passive"))
      (node (ref "R13") (pin "1") (pinfunction "1_1") (pintype "passive"))
    )
    (net (code "20") (name "Net-(C5.-2-Pad3)") (class "Default")
      (node (ref "C5.") (pin "2") (pinfunction "2_2") (pintype "passive"))
      (node (ref "C5.") (pin "3") (pinfunction "2_3") (pintype "passive"))
      (node (ref "R12.") (pin "2") (pinfunction "2_2") (pintype "passive"))
      (node (ref "R13.") (pin "1") (pinfunction "1_1") (pintype "passive"))
    )
    (net (code "21") (name "Net-(C8-2-Pad3)") (class "Default")
      (node (ref "C8") (pin "2") (pinfunction "2_2") (pintype "passive"))
      (node (ref "C8") (pin "3") (pinfunction "2_3") (pintype "passive"))
      (node (ref "C9") (pin "2") (pinfunction "2_2") (pintype "passive"))
      (node (ref "C9") (pin "3") (pinfunction "2_3") (pintype "passive"))
      (node (ref "PR5") (pin "A") (pinfunction "A_A") (pintype "passive"))
      (node (ref "R21") (pin "2") (pinfunction "2_2") (pintype "passive"))
      (node (ref "RE5") (pin "1") (pinfunction "1_1") (pintype "passive"))
    )
    (net (code "22") (name "Net-(C8.-2-Pad3)") (class "Default")
      (node (ref "C8.") (pin "2") (pinfunction "2_2") (pintype "passive"))
      (node (ref "C8.") (pin "3") (pinfunction "2_3") (pintype "passive"))
      (node (ref "C9.") (pin "2") (pinfunction "2_2") (pintype "passive"))
      (node (ref "C9.") (pin "3") (pinfunction "2_3") (pintype "passive"))
      (node (ref "PR5.") (pin "A") (pinfunction "A_A") (pintype "passive"))
      (node (ref "R21.") (pin "2") (pinfunction "2_2") (pintype "passive"))
      (node (ref "RE5.") (pin "1") (pinfunction "1_1") (pintype "passive"))
    )
    (net (code "23") (name "Net-(C10-2-Pad3)") (class "Default")
      (node (ref "C10") (pin "2") (pinfunction "2_2") (pintype "passive"))
      (node (ref "C10") (pin "3") (pinfunction "2_3") (pintype "passive"))
      (node (ref "C11") (pin "2") (pinfunction "2_2") (pintype "passive"))
      (node (ref "C11") (pin "3") (pinfunction "2_3") (pintype "passive"))
      (node (ref "R23") (pin "2") (pinfunction "2_2") (pintype "passive"))
      (node (ref "R23") (pin "3") (pinfunction "2_3") (pintype "passive"))
      (node (ref "R24") (pin "2") (pinfunction "2_2") (pintype "passive"))
      (node (ref "RE7") (pin "1") (pinfunction "1_1") (pintype "passive"))
    )
    (net (code "24") (name "Net-(C10.-2-Pad3)") (class "Default")
      (node (ref "C10.") (pin "2") (pinfunction "2_2") (pintype "passive"))
      (node (ref "C10.") (pin "3") (pinfunction "2_3") (pintype "passive"))
      (node (ref "C11.") (pin "2") (pinfunction "2_2") (pintype "passive"))
      (node (ref "C11.") (pin "3") (pinfunction "2_3") (pintype "passive"))
      (node (ref "R23.") (pin "2") (pinfunction "2_2") (pintype "passive"))
      (node (ref "R23.") (pin "3") (pinfunction "2_3") (pintype "passive"))
      (node (ref "R24.") (pin "2") (pinfunction "2_2") (pintype "passive"))
      (node (ref "RE7.") (pin "1") (pinfunction "1_1") (pintype "passive"))
    )
    (net (code "25") (name "Net-(C12-Pad1)") (class "Default")
      (node (ref "C12") (pin "1") (pinfunction "1_1") (pintype "passive"))
      (node (ref "R30") (pin "1") (pinfunction "1_1") (pintype "passive"))
    )
    (net (code "26") (name "Net-(C12.-Pad1)") (class "Default")
      (node (ref "C12.") (pin "1") (pinfunction "1_1") (pintype "passive"))
      (node (ref "R30.") (pin "1") (pinfunction "1_1") (pintype "passive"))
    )
    (net (code "27") (name "Net-(CE1-Pad1)") (class "Default")
      (node (ref "CE1") (pin "1") (pinfunction "1_1") (pintype "passive"))
      (node (ref "R1") (pin "2") (pinfunction "2_2") (pintype "passive"))
      (node (ref "R1") (pin "3") (pinfunction "2_3") (pintype "passive"))
      (node (ref "RE1") (pin "2") (pinfunction "2_2") (pintype "passive"))
    )
    (net (code "28") (name "Net-(CE1.-Pad1)") (class "Default")
      (node (ref "CE1.") (pin "1") (pinfunction "1_1") (pintype "passive"))
      (node (ref "R1.") (pin "2") (pinfunction "2_2") (pintype "passive"))
      (node (ref "R1.") (pin "3") (pinfunction "2_3") (pintype "passive"))
      (node (ref "RE1.") (pin "2") (pinfunction "2_2") (pintype "passive"))
    )
    (net (code "29") (name "Net-(CE3-2-Pad3)") (class "Default")
      (node (ref "CE3") (pin "2") (pinfunction "2_2") (pintype "passive"))
      (node (ref "CE3") (pin "3") (pinfunction "2_3") (pintype "passive"))
      (node (ref "R21") (pin "1") (pinfunction "1_1") (pintype "passive"))
    )
    (net (code "30") (name "Net-(CE3.-2-Pad3)") (class "Default")
      (node (ref "CE3.") (pin "2") (pinfunction "2_2") (pintype "passive"))
      (node (ref "CE3.") (pin "3") (pinfunction "2_3") (pintype "passive"))
      (node (ref "R21.") (pin "1") (pinfunction "1_1") (pintype "passive"))
    )
    (net (code "31") (name "Net-(D2-PadA)") (class "Default")
      (node (ref "D2") (pin "A") (pinfunction "A_A") (pintype "passive"))
      (node (ref "R10") (pin "1") (pinfunction "1_1") (pintype "passive"))
      (node (ref "R9") (pin "2") (pinfunction "2_2") (pintype "passive"))
    )
    (net (code "32") (name "Net-(D2.-PadA)") (class "Default")
      (node (ref "D2.") (pin "A") (pinfunction "A_A") (pintype "passive"))
      (node (ref "R10.") (pin "1") (pinfunction "1_1") (pintype "passive"))
      (node (ref "R9.") (pin "2") (pinfunction "2_2") (pintype "passive"))
    )
    (net (code "33") (name "Net-(IC1.A-+IN)") (class "Default")
      (node (ref "CE2.") (pin "2") (pinfunction "2_2") (pintype "passive"))
      (node (ref "CE2.") (pin "3") (pinfunction "2_3") (pintype "passive"))
      (node (ref "IC1.") (pin "3") (pinfunction "+IN_3") (pintype "input"))
      (node (ref "RE2.") (pin "2") (pinfunction "2_2") (pintype "passive"))
      (node (ref "RE2.") (pin "3") (pinfunction "2_3") (pintype "passive"))
    )
    (net (code "34") (name "Net-(IC1.A--IN)") (class "Default")
      (node (ref "C1.") (pin "2") (pinfunction "2_2") (pintype "passive"))
      (node (ref "C1.") (pin "3") (pinfunction "2_3") (pintype "passive"))
      (node (ref "IC1.") (pin "2") (pinfunction "-IN_2") (pintype "input"))
      (node (ref "R2.") (pin "1") (pinfunction "1_1") (pintype "passive"))
      (node (ref "RE3.") (pin "2") (pinfunction "2_2") (pintype "passive"))
    )
    (net (code "35") (name "Net-(IC1.A-OUT)") (class "Default")
      (node (ref "C2.") (pin "2") (pinfunction "2_2") (pintype "passive"))
      (node (ref "C2.") (pin "3") (pinfunction "2_3") (pintype "passive"))
      (node (ref "IC1.") (pin "1") (pinfunction "OUT_1") (pintype "output"))
      (node (ref "R2.") (pin "2") (pinfunction "2_2") (pintype "passive"))
      (node (ref "R3.") (pin "1") (pinfunction "1_1") (pintype "passive"))
    )
    (net (code "36") (name "Net-(IC1.B-+IN)") (class "Default")
      (node (ref "IC1.") (pin "5") (pinfunction "+IN_5") (pintype "input"))
      (node (ref "R6.") (pin "2") (pinfunction "2_2") (pintype "passive"))
      (node (ref "R6.") (pin "3") (pinfunction "2_3") (pintype "passive"))
      (node (ref "RE4.") (pin "2") (pinfunction "2_2") (pintype "passive"))
      (node (ref "RE4.") (pin "3") (pinfunction "2_3") (pintype "passive"))
    )
    (net (code "37") (name "Net-(IC1.B--IN)") (class "Default")
      (node (ref "C3.") (pin "2") (pinfunction "2_2") (pintype "passive"))
      (node (ref "C3.") (pin "3") (pinfunction "2_3") (pintype "passive"))
      (node (ref "IC1.") (pin "6") (pinfunction "-IN_6") (pintype "input"))
      (node (ref "R5.") (pin "2") (pinfunction "2_2") (pintype "passive"))
    )
    (net (code "38") (name "Net-(IC1.B-OUT)") (class "Default")
      (node (ref "C4.") (pin "2") (pinfunction "2_2") (pintype "passive"))
      (node (ref "C4.") (pin "3") (pinfunction "2_3") (pintype "passive"))
      (node (ref "IC1.") (pin "7") (pinfunction "OUT_7") (pintype "output"))
      (node (ref "R5.") (pin "1") (pinfunction "1_1") (pintype "passive"))
      (node (ref "R7.") (pin "1") (pinfunction "1_1") (pintype "passive"))
    )
    (net (code "39") (name "Net-(IC1A-+IN)") (class "Default")
      (node (ref "CE2") (pin "2") (pinfunction "2_2") (pintype "passive"))
      (node (ref "CE2") (pin "3") (pinfunction "2_3") (pintype "passive"))
      (node (ref "IC1") (pin "3") (pinfunction "+IN_3") (pintype "input"))
      (node (ref "RE2") (pin "2") (pinfunction "2_2") (pintype "passive"))
      (node (ref "RE2") (pin "3") (pinfunction "2_3") (pintype "passive"))
    )
    (net (code "40") (name "Net-(IC1A--IN)") (class "Default")
      (node (ref "C1") (pin "2") (pinfunction "2_2") (pintype "passive"))
      (node (ref "C1") (pin "3") (pinfunction "2_3") (pintype "passive"))
      (node (ref "IC1") (pin "2") (pinfunction "-IN_2") (pintype "input"))
      (node (ref "R2") (pin "1") (pinfunction "1_1") (pintype "passive"))
      (node (ref "RE3") (pin "2") (pinfunction "2_2") (pintype "passive"))
    )
    (net (code "41") (name "Net-(IC1A-OUT)") (class "Default")
      (node (ref "C2") (pin "2") (pinfunction "2_2") (pintype "passive"))
      (node (ref "C2") (pin "3") (pinfunction "2_3") (pintype "passive"))
      (node (ref "IC1") (pin "1") (pinfunction "OUT_1") (pintype "output"))
      (node (ref "R2") (pin "2") (pinfunction "2_2") (pintype "passive"))
      (node (ref "R3") (pin "1") (pinfunction "1_1") (pintype "passive"))
    )
    (net (code "42") (name "Net-(IC1B-+IN)") (class "Default")
      (node (ref "IC1") (pin "5") (pinfunction "+IN_5") (pintype "input"))
      (node (ref "R6") (pin "2") (pinfunction "2_2") (pintype "passive"))
      (node (ref "R6") (pin "3") (pinfunction "2_3") (pintype "passive"))
      (node (ref "RE4") (pin "2") (pinfunction "2_2") (pintype "passive"))
      (node (ref "RE4") (pin "3") (pinfunction "2_3") (pintype "passive"))
    )
    (net (code "43") (name "Net-(IC1B--IN)") (class "Default")
      (node (ref "C3") (pin "2") (pinfunction "2_2") (pintype "passive"))
      (node (ref "C3") (pin "3") (pinfunction "2_3") (pintype "passive"))
      (node (ref "IC1") (pin "6") (pinfunction "-IN_6") (pintype "input"))
      (node (ref "R5") (pin "2") (pinfunction "2_2") (pintype "passive"))
    )
    (net (code "44") (name "Net-(IC1B-OUT)") (class "Default")
      (node (ref "C4") (pin "2") (pinfunction "2_2") (pintype "passive"))
      (node (ref "C4") (pin "3") (pinfunction "2_3") (pintype "passive"))
      (node (ref "IC1") (pin "7") (pinfunction "OUT_7") (pintype "output"))
      (node (ref "R5") (pin "1") (pinfunction "1_1") (pintype "passive"))
      (node (ref "R7") (pin "1") (pinfunction "1_1") (pintype "passive"))
    )
    (net (code "45") (name "Net-(IC2.A-+IN)") (class "Default")
      (node (ref "D1.") (pin "C") (pinfunction "C_C") (pintype "passive"))
      (node (ref "IC2.") (pin "3") (pinfunction "+IN_3") (pintype "input"))
      (node (ref "R8.") (pin "2") (pinfunction "2_2") (pintype "passive"))
    )
    (net (code "46") (name "Net-(IC2.A--IN)") (class "Default")
      (node (ref "IC2.") (pin "2") (pinfunction "-IN_2") (pintype "input"))
      (node (ref "R10.") (pin "2") (pinfunction "2_2") (pintype "passive"))
      (node (ref "R11.") (pin "1") (pinfunction "1_1") (pintype "passive"))
    )
    (net (code "47") (name "Net-(IC2.A-OUT)") (class "Default")
      (node (ref "IC2.") (pin "1") (pinfunction "OUT_1") (pintype "output"))
      (node (ref "R11.") (pin "2") (pinfunction "2_2") (pintype "passive"))
      (node (ref "R12.") (pin "1") (pinfunction "1_1") (pintype "passive"))
    )
    (net (code "48") (name "Net-(IC2.B--IN)") (class "Default")
      (node (ref "IC2.") (pin "6") (pinfunction "-IN_6") (pintype "input"))
      (node (ref "R7.") (pin "2") (pinfunction "2_2") (pintype "passive"))
      (node (ref "R8.") (pin "1") (pinfunction "1_1") (pintype "passive"))
      (node (ref "R9.") (pin "1") (pinfunction "1_1") (pintype "passive"))
    )
    (net (code "49") (name "Net-(IC2.B-OUT)") (class "Default")
      (node (ref "D1.") (pin "A") (pinfunction "A_A") (pintype "passive"))
      (node (ref "D2.") (pin "C") (pinfunction "C_C") (pintype "passive"))
      (node (ref "IC2.") (pin "7") (pinfunction "OUT_7") (pintype "output"))
    )
    (net (code "50") (name "Net-(IC2A-+IN)") (class "Default")
      (node (ref "D1") (pin "C") (pinfunction "C_C") (pintype "passive"))
      (node (ref "IC2") (pin "3") (pinfunction "+IN_3") (pintype "input"))
      (node (ref "R8") (pin "2") (pinfunction "2_2") (pintype "passive"))
    )
    (net (code "51") (name "Net-(IC2A--IN)") (class "Default")
      (node (ref "IC2") (pin "2") (pinfunction "-IN_2") (pintype "input"))
      (node (ref "R10") (pin "2") (pinfunction "2_2") (pintype "passive"))
      (node (ref "R11") (pin "1") (pinfunction "1_1") (pintype "passive"))
    )
    (net (code "52") (name "Net-(IC2A-OUT)") (class "Default")
      (node (ref "IC2") (pin "1") (pinfunction "OUT_1") (pintype "output"))
      (node (ref "R11") (pin "2") (pinfunction "2_2") (pintype "passive"))
      (node (ref "R12") (pin "1") (pinfunction "1_1") (pintype "passive"))
    )
    (net (code "53") (name "Net-(IC2B--IN)") (class "Default")
      (node (ref "IC2") (pin "6") (pinfunction "-IN_6") (pintype "input"))
      (node (ref "R7") (pin "2") (pinfunction "2_2") (pintype "passive"))
      (node (ref "R8") (pin "1") (pinfunction "1_1") (pintype "passive"))
      (node (ref "R9") (pin "1") (pinfunction "1_1") (pintype "passive"))
    )
    (net (code "54") (name "Net-(IC2B-OUT)") (class "Default")
      (node (ref "D1") (pin "A") (pinfunction "A_A") (pintype "passive"))
      (node (ref "D2") (pin "C") (pinfunction "C_C") (pintype "passive"))
      (node (ref "IC2") (pin "7") (pinfunction "OUT_7") (pintype "output"))
    )
    (net (code "55") (name "Net-(IC3-+IN)") (class "Default")
      (node (ref "C6") (pin "2") (pinfunction "2_2") (pintype "passive"))
      (node (ref "C6") (pin "3") (pinfunction "2_3") (pintype "passive"))
      (node (ref "IC3") (pin "3") (pinfunction "+IN_3") (pintype "input"))
      (node (ref "R13") (pin "2") (pinfunction "2_2") (pintype "passive"))
    )
    (net (code "56") (name "Net-(IC3--IN)") (class "Default")
      (node (ref "C5") (pin "1") (pinfunction "1_1") (pintype "passive"))
      (node (ref "IC3") (pin "2") (pinfunction "-IN_2") (pintype "input"))
      (node (ref "IC3") (pin "6") (pinfunction "OUT_6") (pintype "output"))
      (node (ref "R14") (pin "1") (pinfunction "1_1") (pintype "passive"))
      (node (ref "R15") (pin "2") (pinfunction "2_2") (pintype "passive"))
    )
    (net (code "57") (name "Net-(IC3.-+IN)") (class "Default")
      (node (ref "C6.") (pin "2") (pinfunction "2_2") (pintype "passive"))
      (node (ref "C6.") (pin "3") (pinfunction "2_3") (pintype "passive"))
      (node (ref "IC3.") (pin "3") (pinfunction "+IN_3") (pintype "input"))
      (node (ref "R13.") (pin "2") (pinfunction "2_2") (pintype "passive"))
    )
    (net (code "58") (name "Net-(IC3.--IN)") (class "Default")
      (node (ref "C5.") (pin "1") (pinfunction "1_1") (pintype "passive"))
      (node (ref "IC3.") (pin "2") (pinfunction "-IN_2") (pintype "input"))
      (node (ref "IC3.") (pin "6") (pinfunction "OUT_6") (pintype "output"))
      (node (ref "R14.") (pin "1") (pinfunction "1_1") (pintype "passive"))
      (node (ref "R15.") (pin "2") (pinfunction "2_2") (pintype "passive"))
    )
    (net (code "59") (name "Net-(IC4-+IN)") (class "Default")
      (node (ref "C7") (pin "1") (pinfunction "1_1") (pintype "passive"))
      (node (ref "IC4") (pin "3") (pinfunction "+IN_3") (pintype "input"))
      (node (ref "Q1") (pin "1") (pinfunction "S_1") (pintype "passive"))
    )
    (net (code "60") (name "Net-(IC4--IN)") (class "Default")
      (node (ref "IC4") (pin "2") (pinfunction "-IN_2") (pintype "input"))
      (node (ref "IC4") (pin "6") (pinfunction "OUT_6") (pintype "output"))
      (node (ref "IC5") (pin "3") (pinfunction "+IN_3") (pintype "input"))
      (node (ref "R17") (pin "1") (pinfunction "1_1") (pintype "passive"))
    )
    (net (code "61") (name "Net-(IC4.-+IN)") (class "Default")
      (node (ref "C7.") (pin "1") (pinfunction "1_1") (pintype "passive"))
      (node (ref "IC4.") (pin "3") (pinfunction "+IN_3") (pintype "input"))
      (node (ref "Q1.") (pin "1") (pinfunction "S_1") (pintype "passive"))
    )
    (net (code "62") (name "Net-(IC4.--IN)") (class "Default")
      (node (ref "IC4.") (pin "2") (pinfunction "-IN_2") (pintype "input"))
      (node (ref "IC4.") (pin "6") (pinfunction "OUT_6") (pintype "output"))
      (node (ref "IC5") (pin "5") (pinfunction "+IN_5") (pintype "input"))
      (node (ref "R17.") (pin "1") (pinfunction "1_1") (pintype "passive"))
    )
    (net (code "63") (name "Net-(IC5A--IN)") (class "Default")
      (node (ref "D4") (pin "C") (pinfunction "C_C") (pintype "passive"))
      (node (ref "IC5") (pin "2") (pinfunction "-IN_2") (pintype "input"))
      (node (ref "R18") (pin "1") (pinfunction "1_1") (pintype "passive"))
    )
    (net (code "64") (name "Net-(IC5A-OUT)") (class "Default")
      (node (ref "D4") (pin "A") (pinfunction "A_A") (pintype "passive"))
      (node (ref "IC5") (pin "1") (pinfunction "OUT_1") (pintype "output"))
      (node (ref "PR2") (pin "E") (pinfunction "E_E") (pintype "passive"))
    )
    (net (code "65") (name "Net-(IC5B--IN)") (class "Default")
      (node (ref "D4.") (pin "C") (pinfunction "C_C") (pintype "passive"))
      (node (ref "IC5") (pin "6") (pinfunction "-IN_6") (pintype "input"))
      (node (ref "R18.") (pin "1") (pinfunction "1_1") (pintype "passive"))
    )
    (net (code "66") (name "Net-(IC5B-OUT)") (class "Default")
      (node (ref "D4.") (pin "A") (pinfunction "A_A") (pintype "passive"))
      (node (ref "IC5") (pin "7") (pinfunction "OUT_7") (pintype "output"))
      (node (ref "PR2.") (pin "E") (pinfunction "E_E") (pintype "passive"))
    )
    (net (code "67") (name "Net-(IC6A-+IN)") (class "Default")
      (node (ref "IC6") (pin "3") (pinfunction "+IN_3") (pintype "input"))
      (node (ref "R32") (pin "2") (pinfunction "2_2") (pintype "passive"))
    )
    (net (code "68") (name "Net-(IC6A--IN)") (class "Default")
      (node (ref "IC6") (pin "4") (pinfunction "-IN_4") (pintype "input"))
      (node (ref "R27") (pin "2") (pinfunction "2_2") (pintype "passive"))
      (node (ref "R31") (pin "1") (pinfunction "1_1") (pintype "passive"))
    )
    (net (code "69") (name "Net-(IC6A-AMP{slash}BIAS)") (class "Default")
      (node (ref "IC6") (pin "1") (pinfunction "AMP/BIAS_1") (pintype "passive"))
      (node (ref "R20") (pin "1") (pinfunction "1_1") (pintype "passive"))
    )
    (net (code "70") (name "Net-(IC6A-BUFF{slash}IN)") (class "Default")
      (node (ref "IC6") (pin "7") (pinfunction "BUFF/IN_7") (pintype "input"))
      (node (ref "RV1") (pin "1S") (pinfunction "1S_1S") (pintype "passive"))
    )
    (net (code "71") (name "Net-(IC6A-BUFF{slash}OUT)") (class "Default")
      (node (ref "C12") (pin "2") (pinfunction "2_2") (pintype "passive"))
      (node (ref "C12") (pin "3") (pinfunction "2_3") (pintype "passive"))
      (node (ref "IC6") (pin "8") (pinfunction "BUFF/OUT_8") (pintype "output"))
      (node (ref "R29") (pin "1") (pinfunction "1_1") (pintype "passive"))
    )
    (net (code "72") (name "Net-(IC6A-DIODE{slash}BIAS)") (class "Default")
      (node (ref "IC6") (pin "2") (pinfunction "DIODE/BIAS_2") (pintype "passive"))
      (node (ref "R28") (pin "1") (pinfunction "1_1") (pintype "passive"))
    )
    (net (code "73") (name "Net-(IC6A-OUT)") (class "Default")
      (node (ref "IC6") (pin "5") (pinfunction "OUT_5") (pintype "output"))
      (node (ref "RV1") (pin "1E") (pinfunction "1E_1E") (pintype "passive"))
    )
    (net (code "74") (name "Net-(IC6B-+IN)") (class "Default")
      (node (ref "IC6") (pin "14") (pinfunction "+IN_14") (pintype "input"))
      (node (ref "R32.") (pin "2") (pinfunction "2_2") (pintype "passive"))
    )
    (net (code "75") (name "Net-(IC6B--IN)") (class "Default")
      (node (ref "IC6") (pin "13") (pinfunction "-IN_13") (pintype "input"))
      (node (ref "R27.") (pin "2") (pinfunction "2_2") (pintype "passive"))
      (node (ref "R31.") (pin "1") (pinfunction "1_1") (pintype "passive"))
    )
    (net (code "76") (name "Net-(IC6B-AMP{slash}BIAS)") (class "Default")
      (node (ref "IC6") (pin "16") (pinfunction "AMP/BIAS_16") (pintype "passive"))
      (node (ref "R20.") (pin "1") (pinfunction "1_1") (pintype "passive"))
    )
    (net (code "77") (name "Net-(IC6B-BUFF{slash}IN)") (class "Default")
      (node (ref "IC6") (pin "10") (pinfunction "BUFF/IN_10") (pintype "input"))
      (node (ref "RV1.") (pin "1S") (pinfunction "1S_1S") (pintype "passive"))
    )
    (net (code "78") (name "Net-(IC6B-BUFF{slash}OUT)") (class "Default")
      (node (ref "C12.") (pin "2") (pinfunction "2_2") (pintype "passive"))
      (node (ref "C12.") (pin "3") (pinfunction "2_3") (pintype "passive"))
      (node (ref "IC6") (pin "9") (pinfunction "BUFF/OUT_9") (pintype "output"))
      (node (ref "R29.") (pin "1") (pinfunction "1_1") (pintype "passive"))
    )
    (net (code "79") (name "Net-(IC6B-DIODE{slash}BIAS)") (class "Default")
      (node (ref "IC6") (pin "15") (pinfunction "DIODE/BIAS_15") (pintype "passive"))
      (node (ref "R28.") (pin "1") (pinfunction "1_1") (pintype "passive"))
    )
    (net (code "80") (name "Net-(IC6B-OUT)") (class "Default")
      (node (ref "IC6") (pin "12") (pinfunction "OUT_12") (pintype "output"))
      (node (ref "RV1.") (pin "1E") (pinfunction "1E_1E") (pintype "passive"))
    )
    (net (code "81") (name "Net-(IC7.A-+IN)") (class "Default")
      (node (ref "CE4.") (pin "2") (pinfunction "2_2") (pintype "passive"))
      (node (ref "CE4.") (pin "3") (pinfunction "2_3") (pintype "passive"))
      (node (ref "IC7.") (pin "3") (pinfunction "+IN_3") (pintype "input"))
      (node (ref "RE5.") (pin "2") (pinfunction "2_2") (pintype "passive"))
      (node (ref "RE5.") (pin "3") (pinfunction "2_3") (pintype "passive"))
      (node (ref "RE6.") (pin "2") (pinfunction "2_2") (pintype "passive"))
    )
    (net (code "82") (name "Net-(IC7.A--IN)") (class "Default")
      (node (ref "C8.") (pin "1") (pinfunction "1_1") (pintype "passive"))
      (node (ref "IC7.") (pin "2") (pinfunction "-IN_2") (pintype "input"))
      (node (ref "R22.") (pin "1") (pinfunction "1_1") (pintype "passive"))
      (node (ref "RE10.") (pin "2") (pinfunction "2_2") (pintype "passive"))
    )
    (net (code "83") (name "Net-(IC7.A-OUT)") (class "Default")
      (node (ref "C9.") (pin "1") (pinfunction "1_1") (pintype "passive"))
      (node (ref "IC7.") (pin "1") (pinfunction "OUT_1") (pintype "output"))
      (node (ref "R22.") (pin "2") (pinfunction "2_2") (pintype "passive"))
      (node (ref "R23.") (pin "1") (pinfunction "1_1") (pintype "passive"))
    )
    (net (code "84") (name "Net-(IC7.B-+IN)") (class "Default")
      (node (ref "IC7.") (pin "5") (pinfunction "+IN_5") (pintype "input"))
      (node (ref "R26.") (pin "2") (pinfunction "2_2") (pintype "passive"))
      (node (ref "R26.") (pin "3") (pinfunction "2_3") (pintype "passive"))
      (node (ref "RE7.") (pin "2") (pinfunction "2_2") (pintype "passive"))
      (node (ref "RE7.") (pin "3") (pinfunction "2_3") (pintype "passive"))
    )
    (net (code "85") (name "Net-(IC7.B--IN)") (class "Default")
      (node (ref "C10.") (pin "1") (pinfunction "1_1") (pintype "passive"))
      (node (ref "IC7.") (pin "6") (pinfunction "-IN_6") (pintype "input"))
      (node (ref "R25.") (pin "1") (pinfunction "1_1") (pintype "passive"))
    )
    (net (code "86") (name "Net-(IC7.B-OUT)") (class "Default")
      (node (ref "C11.") (pin "1") (pinfunction "1_1") (pintype "passive"))
      (node (ref "IC7.") (pin "7") (pinfunction "OUT_7") (pintype "output"))
      (node (ref "R25.") (pin "2") (pinfunction "2_2") (pintype "passive"))
      (node (ref "R27.") (pin "1") (pinfunction "1_1") (pintype "passive"))
    )
    (net (code "87") (name "Net-(IC7A-+IN)") (class "Default")
      (node (ref "CE4") (pin "2") (pinfunction "2_2") (pintype "passive"))
      (node (ref "CE4") (pin "3") (pinfunction "2_3") (pintype "passive"))
      (node (ref "IC7") (pin "3") (pinfunction "+IN_3") (pintype "input"))
      (node (ref "RE5") (pin "2") (pinfunction "2_2") (pintype "passive"))
      (node (ref "RE5") (pin "3") (pinfunction "2_3") (pintype "passive"))
      (node (ref "RE6") (pin "2") (pinfunction "2_2") (pintype "passive"))
    )
    (net (code "88") (name "Net-(IC7A--IN)") (class "Default")
      (node (ref "C8") (pin "1") (pinfunction "1_1") (pintype "passive"))
      (node (ref "IC7") (pin "2") (pinfunction "-IN_2") (pintype "input"))
      (node (ref "R22") (pin "1") (pinfunction "1_1") (pintype "passive"))
      (node (ref "RE10") (pin "2") (pinfunction "2_2") (pintype "passive"))
    )
    (net (code "89") (name "Net-(IC7A-OUT)") (class "Default")
      (node (ref "C9") (pin "1") (pinfunction "1_1") (pintype "passive"))
      (node (ref "IC7") (pin "1") (pinfunction "OUT_1") (pintype "output"))
      (node (ref "R22") (pin "2") (pinfunction "2_2") (pintype "passive"))
      (node (ref "R23") (pin "1") (pinfunction "1_1") (pintype "passive"))
    )
    (net (code "90") (name "Net-(IC7B-+IN)") (class "Default")
      (node (ref "IC7") (pin "5") (pinfunction "+IN_5") (pintype "input"))
      (node (ref "R26") (pin "2") (pinfunction "2_2") (pintype "passive"))
      (node (ref "R26") (pin "3") (pinfunction "2_3") (pintype "passive"))
      (node (ref "RE7") (pin "2") (pinfunction "2_2") (pintype "passive"))
      (node (ref "RE7") (pin "3") (pinfunction "2_3") (pintype "passive"))
    )
    (net (code "91") (name "Net-(IC7B--IN)") (class "Default")
      (node (ref "C10") (pin "1") (pinfunction "1_1") (pintype "passive"))
      (node (ref "IC7") (pin "6") (pinfunction "-IN_6") (pintype "input"))
      (node (ref "R25") (pin "1") (pinfunction "1_1") (pintype "passive"))
    )
    (net (code "92") (name "Net-(IC7B-OUT)") (class "Default")
      (node (ref "C11") (pin "1") (pinfunction "1_1") (pintype "passive"))
      (node (ref "IC7") (pin "7") (pinfunction "OUT_7") (pintype "output"))
      (node (ref "R25") (pin "2") (pinfunction "2_2") (pintype "passive"))
      (node (ref "R27") (pin "1") (pinfunction "1_1") (pintype "passive"))
    )
    (net (code "93") (name "Net-(PR2-PadA)") (class "Default")
      (node (ref "PR2") (pin "A") (pinfunction "A_A") (pintype "passive"))
      (node (ref "PR2") (pin "S") (pinfunction "S_S") (pintype "passive"))
      (node (ref "Q2") (pin "E") (pinfunction "E_E") (pintype "passive"))
      (node (ref "R19") (pin "1") (pinfunction "1_1") (pintype "passive"))
    )
    (net (code "94") (name "Net-(PR2.-PadA)") (class "Default")
      (node (ref "PR2.") (pin "A") (pinfunction "A_A") (pintype "passive"))
      (node (ref "PR2.") (pin "S") (pinfunction "S_S") (pintype "passive"))
      (node (ref "Q2.") (pin "E") (pinfunction "E_E") (pintype "passive"))
      (node (ref "R19.") (pin "1") (pinfunction "1_1") (pintype "passive"))
    )
    (net (code "95") (name "Net-(PR3-PadS)") (class "Default")
      (node (ref "PR3") (pin "S") (pinfunction "S_S") (pintype "passive"))
      (node (ref "R19") (pin "2") (pinfunction "2_2") (pintype "passive"))
    )
    (net (code "96") (name "Net-(PR3.-PadS)") (class "Default")
      (node (ref "PR3.") (pin "S") (pinfunction "S_S") (pintype "passive"))
      (node (ref "R19.") (pin "2") (pinfunction "2_2") (pintype "passive"))
    )
    (net (code "97") (name "Net-(PR4-PadA)") (class "Default")
      (node (ref "PR4") (pin "A") (pinfunction "A_A") (pintype "passive"))
      (node (ref "R31") (pin "2") (pinfunction "2_2") (pintype "passive"))
    )
    (net (code "98") (name "Net-(PR4-PadE)") (class "Default")
      (node (ref "PR4") (pin "E") (pinfunction "E_E") (pintype "passive"))
      (node (ref "R32") (pin "1") (pinfunction "1_1") (pintype "passive"))
    )
    (net (code "99") (name "Net-(PR4.-PadA)") (class "Default")
      (node (ref "PR4.") (pin "A") (pinfunction "A_A") (pintype "passive"))
      (node (ref "R31.") (pin "2") (pinfunction "2_2") (pintype "passive"))
    )
    (net (code "100") (name "Net-(PR4.-PadE)") (class "Default")
      (node (ref "PR4.") (pin "E") (pinfunction "E_E") (pintype "passive"))
      (node (ref "R32.") (pin "1") (pinfunction "1_1") (pintype "passive"))
    )
    (net (code "101") (name "Net-(Q1-D)") (class "Default")
      (node (ref "Q1") (pin "3") (pinfunction "D_3") (pintype "passive"))
      (node (ref "R15") (pin "1") (pinfunction "1_1") (pintype "passive"))
      (node (ref "R16") (pin "2") (pinfunction "2_2") (pintype "passive"))
    )
    (net (code "102") (name "Net-(Q1-G)") (class "Default")
      (node (ref "D3") (pin "A") (pinfunction "A_A") (pintype "passive"))
      (node (ref "Q1") (pin "2") (pinfunction "G_2") (pintype "passive"))
      (node (ref "R17") (pin "2") (pinfunction "2_2") (pintype "passive"))
    )
    (net (code "103") (name "Net-(Q1.-D)") (class "Default")
      (node (ref "Q1.") (pin "3") (pinfunction "D_3") (pintype "passive"))
      (node (ref "R15.") (pin "1") (pinfunction "1_1") (pintype "passive"))
      (node (ref "R16.") (pin "2") (pinfunction "2_2") (pintype "passive"))
    )
    (net (code "104") (name "Net-(Q1.-G)") (class "Default")
      (node (ref "D3.") (pin "A") (pinfunction "A_A") (pintype "passive"))
      (node (ref "Q1.") (pin "2") (pinfunction "G_2") (pintype "passive"))
      (node (ref "R17.") (pin "2") (pinfunction "2_2") (pintype "passive"))
    )
    (net (code "105") (name "Net-(Q2-PadC)") (class "Default")
      (node (ref "Q2") (pin "C") (pinfunction "C_C") (pintype "passive"))
      (node (ref "R20") (pin "2") (pinfunction "2_2") (pintype "passive"))
    )
    (net (code "106") (name "Net-(Q2.-PadC)") (class "Default")
      (node (ref "Q2.") (pin "C") (pinfunction "C_C") (pintype "passive"))
      (node (ref "R20.") (pin "2") (pinfunction "2_2") (pintype "passive"))
    )
    (net (code "107") (name "unconnected-(IC3-ON1-Pad1)") (class "Default")
      (node (ref "IC3") (pin "1") (pinfunction "ON1_1") (pintype "passive"))
    )
    (net (code "108") (name "unconnected-(IC3-ON2-Pad5)") (class "Default")
      (node (ref "IC3") (pin "5") (pinfunction "ON2_5") (pintype "passive"))
    )
    (net (code "109") (name "unconnected-(IC3-OPT-Pad8)") (class "Default")
      (node (ref "IC3") (pin "8") (pinfunction "OPT_8") (pintype "passive"))
    )
    (net (code "110") (name "unconnected-(IC3.-ON1-Pad1)") (class "Default")
      (node (ref "IC3.") (pin "1") (pinfunction "ON1_1") (pintype "passive"))
    )
    (net (code "111") (name "unconnected-(IC3.-ON2-Pad5)") (class "Default")
      (node (ref "IC3.") (pin "5") (pinfunction "ON2_5") (pintype "passive"))
    )
    (net (code "112") (name "unconnected-(IC3.-OPT-Pad8)") (class "Default")
      (node (ref "IC3.") (pin "8") (pinfunction "OPT_8") (pintype "passive"))
    )
    (net (code "113") (name "unconnected-(IC4-ON1-Pad1)") (class "Default")
      (node (ref "IC4") (pin "1") (pinfunction "ON1_1") (pintype "passive"))
    )
    (net (code "114") (name "unconnected-(IC4-ON2-Pad5)") (class "Default")
      (node (ref "IC4") (pin "5") (pinfunction "ON2_5") (pintype "passive"))
    )
    (net (code "115") (name "unconnected-(IC4-OPT-Pad8)") (class "Default")
      (node (ref "IC4") (pin "8") (pinfunction "OPT_8") (pintype "passive"))
    )
    (net (code "116") (name "unconnected-(IC4.-ON1-Pad1)") (class "Default")
      (node (ref "IC4.") (pin "1") (pinfunction "ON1_1") (pintype "passive"))
    )
    (net (code "117") (name "unconnected-(IC4.-ON2-Pad5)") (class "Default")
      (node (ref "IC4.") (pin "5") (pinfunction "ON2_5") (pintype "passive"))
    )
    (net (code "118") (name "unconnected-(IC4.-OPT-Pad8)") (class "Default")
      (node (ref "IC4.") (pin "8") (pinfunction "OPT_8") (pintype "passive"))
    )
  )
)
